# Template.net
KiCad netlist of a schematic drawn in Altium Designer
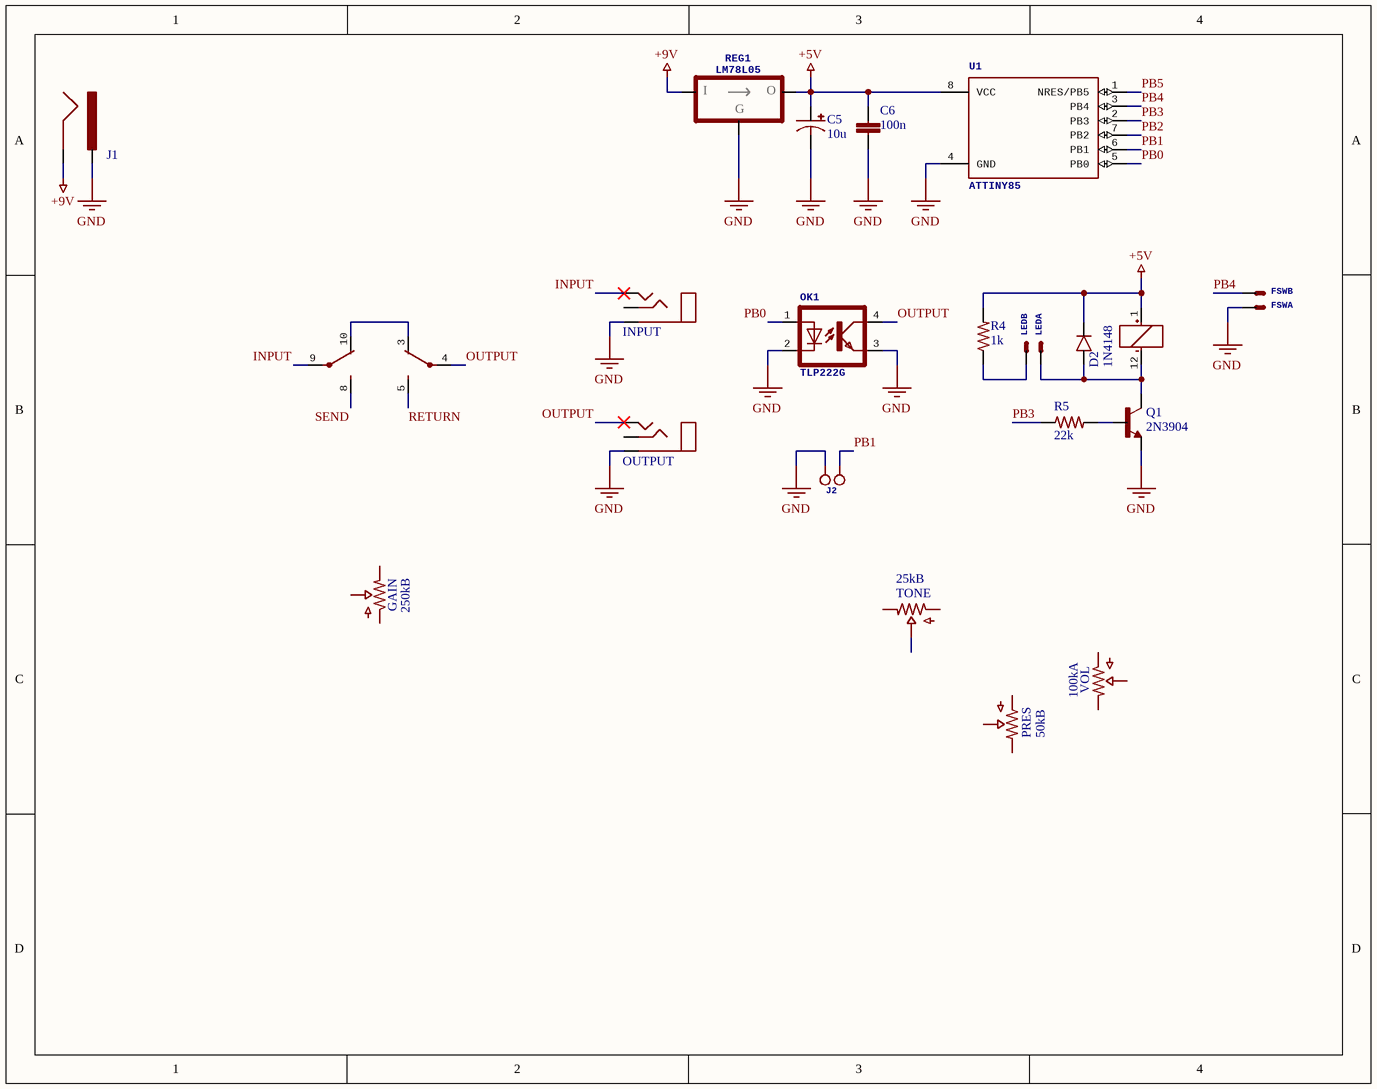
[diagram p0: Template.SchDoc]

(export (version "E")
  (design (tool "Eeschema 10.0.6"))
  (components
    (comp (ref "C5")
      (value "10u")
      (footprint "ELEC_040_020")
      (libsource (lib "Pedals") (part "ELEC_10u_50V"))
    )
    (comp (ref "C6") (value "100n") (footprint "CER_050") (libsource (lib "Pedals") (part "CER_100n")))
    (comp (ref "D2") (value "1N4148") (footprint "DO35_2") (libsource (lib "Pedals") (part "1N4148")))
    (comp (ref "FSW") (value "~") (footprint "JST-XH-02") (libsource (lib "Pedals") (part "JST-XH-02")))
    (comp (ref "GAIN")
      (value "250kB")
      (footprint "ALPHA_16mm_BOTTOM")
      (libsource (lib "Pedals") (part "ALPHA_16mm"))
    )
    (comp (ref "INPUT") (value "~") (footprint "STEREO") (libsource (lib "Pedals") (part "STEREO")))
    (comp (ref "J1") (value "DC_JACK") (footprint "DC_JACK") (libsource (lib "Pedals") (part "DC_JACK")))
    (comp (ref "J2")
      (value "HEADER_2PINS")
      (footprint "HEADER_2PINS")
      (libsource (lib "Pedals") (part "HEADER_2PINS"))
    )
    (comp (ref "K1") (value "~") (footprint "NA5") (libsource (lib "") (part "NA5W-K_1")))
    (comp (ref "LED") (value "~") (footprint "JST-XH-02") (libsource (lib "Pedals") (part "JST-XH-02")))
    (comp (ref "OK1") (value "TLP222G") (footprint "DIL4") (libsource (lib "Pedals") (part "TLP222G")))
    (comp (ref "OUTPUT") (value "~") (footprint "STEREO") (libsource (lib "Pedals") (part "STEREO")))
    (comp (ref "PRES")
      (value "50kB")
      (footprint "ALPHA_16mm_BOTTOM")
      (libsource (lib "Pedals") (part "ALPHA_16mm"))
    )
    (comp (ref "Q1") (value "2N3904") (footprint "TO92") (libsource (lib "Pedals") (part "2N3904")))
    (comp (ref "R4") (value "1k") (footprint "R_3_1k_025W") (libsource (lib "Pedals") (part "R_3_1k_025W")))
    (comp (ref "R5")
      (value "22k")
      (footprint "R_3_22k_025W")
      (libsource (lib "Pedals") (part "R_3_22k_025W"))
    )
    (comp (ref "REG1") (value "LM78L05") (footprint "TO92") (libsource (lib "Pedals") (part "LM78L05")))
    (comp (ref "TONE")
      (value "25kB")
      (footprint "ALPHA_16mm_BOTTOM")
      (libsource (lib "Pedals") (part "ALPHA_16mm"))
    )
    (comp (ref "U1") (value "ATTINY85") (footprint "DIP8") (libsource (lib "Pedals") (part "ATTINY85")))
    (comp (ref "VOL")
      (value "100kA")
      (footprint "ALPHA_16mm_BOTTOM")
      (libsource (lib "Pedals") (part "ALPHA_16mm"))
    )
  )
  (nets
    (net (code "1") (name "+5V") (class "Default")
      (node (ref "C5") (pin "+") (pinfunction "+_+") (pintype "passive"))
      (node (ref "C6") (pin "2") (pinfunction "2_2") (pintype "passive"))
      (node (ref "D2") (pin "C") (pinfunction "C_C") (pintype "passive"))
      (node (ref "K1") (pin "1") (pinfunction "+_1") (pintype "passive"))
      (node (ref "R4") (pin "2") (pinfunction "2_2") (pintype "passive"))
      (node (ref "REG1") (pin "3") (pinfunction "VO_3") (pintype "power_in"))
      (node (ref "U1") (pin "8") (pinfunction "VCC_8") (pintype "power_in"))
    )
    (net (code "2") (name "+9V") (class "Default")
      (node (ref "J1") (pin "GND") (pinfunction "GND_GND") (pintype "passive"))
      (node (ref "REG1") (pin "1") (pinfunction "VI_1") (pintype "power_in"))
    )
    (net (code "3") (name "/INPUT") (class "Default")
      (node (ref "INPUT") (pin "T") (pinfunction "T_T") (pintype "passive"))
      (node (ref "K1") (pin "9") (pinfunction "P_9") (pintype "passive"))
    )
    (net (code "4") (name "/OUTPUT") (class "Default")
      (node (ref "K1") (pin "4") (pinfunction "P_4") (pintype "passive"))
      (node (ref "OK1") (pin "4") (pinfunction "COL_4") (pintype "passive"))
      (node (ref "OUTPUT") (pin "T") (pinfunction "T_T") (pintype "passive"))
    )
    (net (code "5") (name "/PB0") (class "Default")
      (node (ref "OK1") (pin "1") (pinfunction "A_1") (pintype "passive"))
      (node (ref "U1") (pin "5") (pinfunction "PB0_5") (pintype "bidirectional"))
    )
    (net (code "6") (name "/PB1") (class "Default")
      (node (ref "J2") (pin "2") (pinfunction "2_2") (pintype "passive"))
      (node (ref "U1") (pin "6") (pinfunction "PB1_6") (pintype "bidirectional"))
    )
    (net (code "7") (name "/PB2") (class "Default")
      (node (ref "U1") (pin "7") (pinfunction "PB2_7") (pintype "bidirectional"))
    )
    (net (code "8") (name "/PB3") (class "Default")
      (node (ref "R5") (pin "1") (pinfunction "1_1") (pintype "passive"))
      (node (ref "U1") (pin "2") (pinfunction "PB3_2") (pintype "bidirectional"))
    )
    (net (code "9") (name "/PB4") (class "Default")
      (node (ref "FSW") (pin "1") (pinfunction "S_1") (pintype "passive"))
      (node (ref "U1") (pin "3") (pinfunction "PB4_3") (pintype "bidirectional"))
    )
    (net (code "10") (name "/PB5") (class "Default")
      (node (ref "U1") (pin "1") (pinfunction "NRES/PB5_1") (pintype "bidirectional"))
    )
    (net (code "11") (name "/RETURN") (class "Default")
      (node (ref "K1") (pin "5") (pinfunction "S_5") (pintype "passive"))
    )
    (net (code "12") (name "/SEND") (class "Default")
      (node (ref "K1") (pin "8") (pinfunction "S_8") (pintype "passive"))
    )
    (net (code "13") (name "GND") (class "Default")
      (node (ref "C5") (pin "-") (pinfunction "-_-") (pintype "passive"))
      (node (ref "C6") (pin "1") (pinfunction "1_1") (pintype "passive"))
      (node (ref "FSW") (pin "2") (pinfunction "S_2") (pintype "passive"))
      (node (ref "INPUT") (pin "S") (pinfunction "S_S") (pintype "passive"))
      (node (ref "J1") (pin "PWR") (pinfunction "PWR_PWR") (pintype "passive"))
      (node (ref "J2") (pin "1") (pinfunction "1_1") (pintype "passive"))
      (node (ref "OK1") (pin "2") (pinfunction "C_2") (pintype "passive"))
      (node (ref "OK1") (pin "3") (pinfunction "EMIT_3") (pintype "passive"))
      (node (ref "OUTPUT") (pin "S") (pinfunction "S_S") (pintype "passive"))
      (node (ref "Q1") (pin "3") (pinfunction "E_3") (pintype "passive"))
      (node (ref "REG1") (pin "2") (pinfunction "GND_2") (pintype "power_in"))
      (node (ref "U1") (pin "4") (pinfunction "GND_4") (pintype "power_in"))
    )
    (net (code "14") (name "Net-(K1A--)") (class "Default")
      (node (ref "D2") (pin "A") (pinfunction "A_A") (pintype "passive"))
      (node (ref "K1") (pin "12") (pinfunction "-_12") (pintype "passive"))
      (node (ref "LED") (pin "2") (pinfunction "S_2") (pintype "passive"))
      (node (ref "Q1") (pin "1") (pinfunction "C_1") (pintype "passive"))
    )
    (net (code "15") (name "Net-(K1B-O)") (class "Default")
      (node (ref "K1") (pin "10") (pinfunction "O_10") (pintype "passive"))
      (node (ref "K1") (pin "3") (pinfunction "O_3") (pintype "passive"))
    )
    (net (code "16") (name "Net-(LEDB-S)") (class "Default")
      (node (ref "LED") (pin "1") (pinfunction "S_1") (pintype "passive"))
      (node (ref "R4") (pin "1") (pinfunction "1_1") (pintype "passive"))
    )
    (net (code "17") (name "Net-(Q1-B)") (class "Default")
      (node (ref "Q1") (pin "2") (pinfunction "B_2") (pintype "passive"))
      (node (ref "R5") (pin "2") (pinfunction "2_2") (pintype "passive"))
    )
    (net (code "18") (name "unconnected-(GAIN-Pad1)") (class "Default")
      (node (ref "GAIN") (pin "1") (pinfunction "1_1") (pintype "passive"))
    )
    (net (code "19") (name "unconnected-(GAIN-Pad2)") (class "Default")
      (node (ref "GAIN") (pin "2") (pinfunction "2_2") (pintype "passive"))
    )
    (net (code "20") (name "unconnected-(GAIN-Pad3)") (class "Default")
      (node (ref "GAIN") (pin "3") (pinfunction "3_3") (pintype "passive"))
    )
    (net (code "21") (name "unconnected-(INPUT-PadR)") (class "Default")
      (node (ref "INPUT") (pin "R") (pinfunction "R_R") (pintype "passive"))
    )
    (net (code "22") (name "unconnected-(OUTPUT-PadR)") (class "Default")
      (node (ref "OUTPUT") (pin "R") (pinfunction "R_R") (pintype "passive"))
    )
    (net (code "23") (name "unconnected-(PRES-Pad1)") (class "Default")
      (node (ref "PRES") (pin "1") (pinfunction "1_1") (pintype "passive"))
    )
    (net (code "24") (name "unconnected-(PRES-Pad2)") (class "Default")
      (node (ref "PRES") (pin "2") (pinfunction "2_2") (pintype "passive"))
    )
    (net (code "25") (name "unconnected-(PRES-Pad3)") (class "Default")
      (node (ref "PRES") (pin "3") (pinfunction "3_3") (pintype "passive"))
    )
    (net (code "26") (name "unconnected-(TONE-Pad1)") (class "Default")
      (node (ref "TONE") (pin "1") (pinfunction "1_1") (pintype "passive"))
    )
    (net (code "27") (name "unconnected-(TONE-Pad2)") (class "Default")
      (node (ref "TONE") (pin "2") (pinfunction "2_2") (pintype "passive"))
    )
    (net (code "28") (name "unconnected-(TONE-Pad3)") (class "Default")
      (node (ref "TONE") (pin "3") (pinfunction "3_3") (pintype "passive"))
    )
    (net (code "29") (name "unconnected-(VOL-Pad1)") (class "Default")
      (node (ref "VOL") (pin "1") (pinfunction "1_1") (pintype "passive"))
    )
    (net (code "30") (name "unconnected-(VOL-Pad2)") (class "Default")
      (node (ref "VOL") (pin "2") (pinfunction "2_2") (pintype "passive"))
    )
    (net (code "31") (name "unconnected-(VOL-Pad3)") (class "Default")
      (node (ref "VOL") (pin "3") (pinfunction "3_3") (pintype "passive"))
    )
  )
)
